# Single_12V.net
KiCad netlist of a schematic drawn in Altium Designer
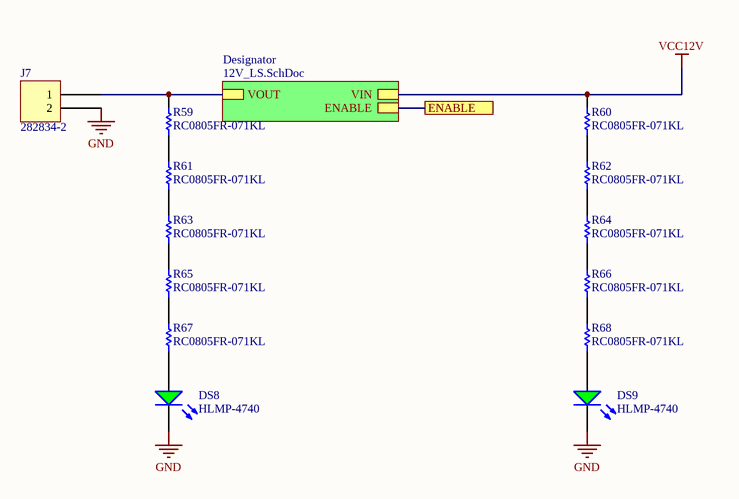
[diagram p0: Single_12V.SchDoc]

(export (version "E")
  (design (tool "Eeschema 10.0.6"))
  (components
    (comp (ref "DS8")
      (value "HLMP-4740")
      (footprint "AVAG-HLMP-4740")
      (description "T-1 3/4 (5 mm) Low Current LED Lamp, Green, 1.9 V, -20 to 100 degC, 2-Pin THD, RoHS, Bulk")
      (fields (field (name "MANUFACTURER") "AvagoTechnologies"))
      (libsource (lib "Altium Content Vault") (part "LED-GREEN-AK-2"))
    )
    (comp (ref "DS9")
      (value "HLMP-4740")
      (footprint "AVAG-HLMP-4740")
      (description "T-1 3/4 (5 mm) Low Current LED Lamp, Green, 1.9 V, -20 to 100 degC, 2-Pin THD, RoHS, Bulk")
      (fields (field (name "MANUFACTURER") "AvagoTechnologies"))
      (libsource (lib "Altium Content Vault") (part "LED-GREEN-AK-2"))
    )
    (comp (ref "J7")
      (value "282834-2")
      (footprint "TE 282834-2")
      (description "TERM BLK 2P SIDE ENT 2.54MM PCB")
      (fields (field (name "MANUFACTURER") "TE Connectivity AMP Connectors") (field (name "VOLTAGE") "150V"))
      (libsource (lib "Celestial Altium Library - altium_library") (part "2 Pin"))
    )
    (comp (ref "R59")
      (value "RC0805FR-071KL")
      (footprint "RESC2013X60X35ML10T20")
      (description "Chip Resistor, 1 KOhm, +/- 1%, 125 mW, -55 to 155 degC, 0805 (2012 Metric), RoHS, Tape and Reel")
      (fields (field (name "TOLERANCE") "1%") (field (name "MANUFACTURER") "Yageo"))
      (libsource (lib "Altium Content Vault") (part "RES-2"))
    )
    (comp (ref "R60")
      (value "RC0805FR-071KL")
      (footprint "RESC2013X60X35ML10T20")
      (description "Chip Resistor, 1 KOhm, +/- 1%, 125 mW, -55 to 155 degC, 0805 (2012 Metric), RoHS, Tape and Reel")
      (fields (field (name "TOLERANCE") "1%") (field (name "MANUFACTURER") "Yageo"))
      (libsource (lib "Altium Content Vault") (part "RES-2"))
    )
    (comp (ref "R61")
      (value "RC0805FR-071KL")
      (footprint "RESC2013X60X35ML10T20")
      (description "Chip Resistor, 1 KOhm, +/- 1%, 125 mW, -55 to 155 degC, 0805 (2012 Metric), RoHS, Tape and Reel")
      (fields (field (name "TOLERANCE") "1%") (field (name "MANUFACTURER") "Yageo"))
      (libsource (lib "Altium Content Vault") (part "RES-2"))
    )
    (comp (ref "R62")
      (value "RC0805FR-071KL")
      (footprint "RESC2013X60X35ML10T20")
      (description "Chip Resistor, 1 KOhm, +/- 1%, 125 mW, -55 to 155 degC, 0805 (2012 Metric), RoHS, Tape and Reel")
      (fields (field (name "TOLERANCE") "1%") (field (name "MANUFACTURER") "Yageo"))
      (libsource (lib "Altium Content Vault") (part "RES-2"))
    )
    (comp (ref "R63")
      (value "RC0805FR-071KL")
      (footprint "RESC2013X60X35ML10T20")
      (description "Chip Resistor, 1 KOhm, +/- 1%, 125 mW, -55 to 155 degC, 0805 (2012 Metric), RoHS, Tape and Reel")
      (fields (field (name "TOLERANCE") "1%") (field (name "MANUFACTURER") "Yageo"))
      (libsource (lib "Altium Content Vault") (part "RES-2"))
    )
    (comp (ref "R64")
      (value "RC0805FR-071KL")
      (footprint "RESC2013X60X35ML10T20")
      (description "Chip Resistor, 1 KOhm, +/- 1%, 125 mW, -55 to 155 degC, 0805 (2012 Metric), RoHS, Tape and Reel")
      (fields (field (name "TOLERANCE") "1%") (field (name "MANUFACTURER") "Yageo"))
      (libsource (lib "Altium Content Vault") (part "RES-2"))
    )
    (comp (ref "R65")
      (value "RC0805FR-071KL")
      (footprint "RESC2013X60X35ML10T20")
      (description "Chip Resistor, 1 KOhm, +/- 1%, 125 mW, -55 to 155 degC, 0805 (2012 Metric), RoHS, Tape and Reel")
      (fields (field (name "TOLERANCE") "1%") (field (name "MANUFACTURER") "Yageo"))
      (libsource (lib "Altium Content Vault") (part "RES-2"))
    )
    (comp (ref "R66")
      (value "RC0805FR-071KL")
      (footprint "RESC2013X60X35ML10T20")
      (description "Chip Resistor, 1 KOhm, +/- 1%, 125 mW, -55 to 155 degC, 0805 (2012 Metric), RoHS, Tape and Reel")
      (fields (field (name "TOLERANCE") "1%") (field (name "MANUFACTURER") "Yageo"))
      (libsource (lib "Altium Content Vault") (part "RES-2"))
    )
    (comp (ref "R67")
      (value "RC0805FR-071KL")
      (footprint "RESC2013X60X35ML10T20")
      (description "Chip Resistor, 1 KOhm, +/- 1%, 125 mW, -55 to 155 degC, 0805 (2012 Metric), RoHS, Tape and Reel")
      (fields (field (name "TOLERANCE") "1%") (field (name "MANUFACTURER") "Yageo"))
      (libsource (lib "Altium Content Vault") (part "RES-2"))
    )
    (comp (ref "R68")
      (value "RC0805FR-071KL")
      (footprint "RESC2013X60X35ML10T20")
      (description "Chip Resistor, 1 KOhm, +/- 1%, 125 mW, -55 to 155 degC, 0805 (2012 Metric), RoHS, Tape and Reel")
      (fields (field (name "TOLERANCE") "1%") (field (name "MANUFACTURER") "Yageo"))
      (libsource (lib "Altium Content Vault") (part "RES-2"))
    )
  )
  (nets
    (net (code "2") (name "/VOUT") (class "Default")
      (node (ref "J7") (pin "1") (pinfunction "1_1") (pintype "passive"))
      (node (ref "R59") (pin "2") (pinfunction "2_2") (pintype "passive"))
    )
    (net (code "3") (name "GND") (class "Default")
      (node (ref "DS8") (pin "2") (pinfunction "K_2") (pintype "passive"))
      (node (ref "DS9") (pin "2") (pinfunction "K_2") (pintype "passive"))
      (node (ref "J7") (pin "2") (pinfunction "2_2") (pintype "passive"))
    )
    (net (code "4") (name "Net-(DS8-A)") (class "Default")
      (node (ref "DS8") (pin "1") (pinfunction "A_1") (pintype "passive"))
      (node (ref "R67") (pin "1") (pinfunction "1_1") (pintype "passive"))
    )
    (net (code "5") (name "Net-(DS9-A)") (class "Default")
      (node (ref "DS9") (pin "1") (pinfunction "A_1") (pintype "passive"))
      (node (ref "R68") (pin "1") (pinfunction "1_1") (pintype "passive"))
    )
    (net (code "6") (name "Net-(R59-Pad1)") (class "Default")
      (node (ref "R59") (pin "1") (pinfunction "1_1") (pintype "passive"))
      (node (ref "R61") (pin "2") (pinfunction "2_2") (pintype "passive"))
    )
    (net (code "7") (name "Net-(R60-Pad1)") (class "Default")
      (node (ref "R60") (pin "1") (pinfunction "1_1") (pintype "passive"))
      (node (ref "R62") (pin "2") (pinfunction "2_2") (pintype "passive"))
    )
    (net (code "8") (name "Net-(R61-Pad1)") (class "Default")
      (node (ref "R61") (pin "1") (pinfunction "1_1") (pintype "passive"))
      (node (ref "R63") (pin "2") (pinfunction "2_2") (pintype "passive"))
    )
    (net (code "9") (name "Net-(R62-Pad1)") (class "Default")
      (node (ref "R62") (pin "1") (pinfunction "1_1") (pintype "passive"))
      (node (ref "R64") (pin "2") (pinfunction "2_2") (pintype "passive"))
    )
    (net (code "10") (name "Net-(R63-Pad1)") (class "Default")
      (node (ref "R63") (pin "1") (pinfunction "1_1") (pintype "passive"))
      (node (ref "R65") (pin "2") (pinfunction "2_2") (pintype "passive"))
    )
    (net (code "11") (name "Net-(R64-Pad1)") (class "Default")
      (node (ref "R64") (pin "1") (pinfunction "1_1") (pintype "passive"))
      (node (ref "R66") (pin "2") (pinfunction "2_2") (pintype "passive"))
    )
    (net (code "12") (name "Net-(R65-Pad1)") (class "Default")
      (node (ref "R65") (pin "1") (pinfunction "1_1") (pintype "passive"))
      (node (ref "R67") (pin "2") (pinfunction "2_2") (pintype "passive"))
    )
    (net (code "13") (name "Net-(R66-Pad1)") (class "Default")
      (node (ref "R66") (pin "1") (pinfunction "1_1") (pintype "passive"))
      (node (ref "R68") (pin "2") (pinfunction "2_2") (pintype "passive"))
    )
    (net (code "14") (name "VCC12V") (class "Default")
      (node (ref "R60") (pin "2") (pinfunction "2_2") (pintype "passive"))
    )
  )
)
